# capacitive_touch_avr.net
KiCad netlist of a schematic drawn in EAGLE
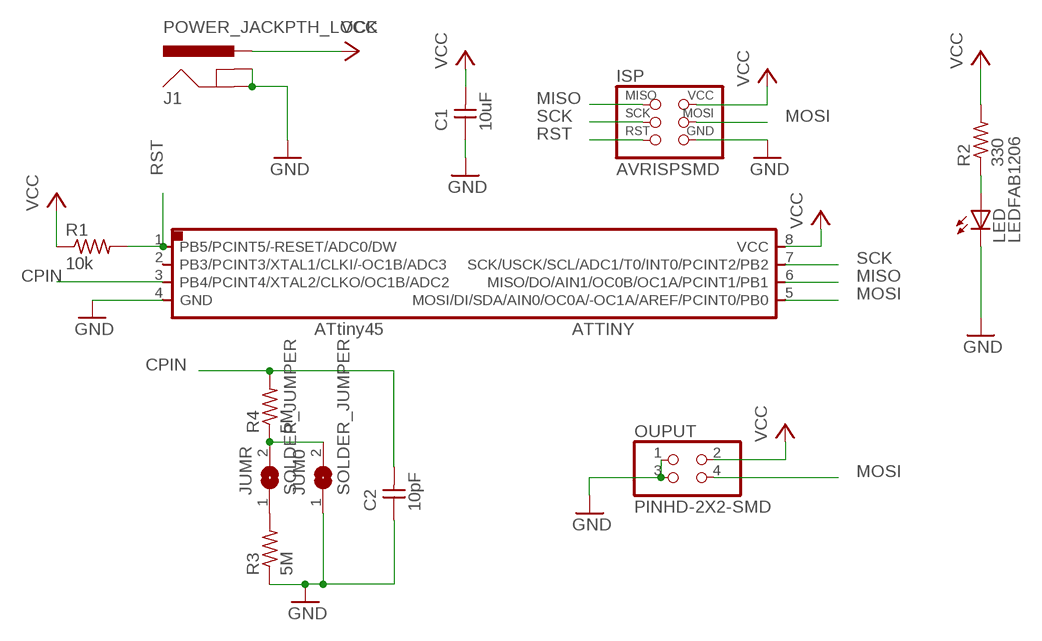
[diagram p0: schematic, sheet 1]

(export (version "E")
  (design (tool "Eeschema 10.0.6"))
  (components
    (comp (ref "ATTINY")
      (value "ATTINY45SI")
      (footprint "eagle-import:SOIC8")
      (libsource (lib "eagle-import") (part "ATTINY45SI"))
    )
    (comp (ref "C1")
      (value "10uF")
      (footprint "eagle-import:C1206FAB")
      (libsource (lib "eagle-import") (part "CAP-UNPOLARIZEDFAB"))
    )
    (comp (ref "C2")
      (value "10pF")
      (footprint "eagle-import:C1206FAB")
      (libsource (lib "eagle-import") (part "CAP-UNPOLARIZEDFAB"))
    )
    (comp (ref "ISP")
      (value "AVRISPSMD")
      (footprint "eagle-import:2X03SMD")
      (libsource (lib "eagle-import") (part "AVRISPSMD"))
    )
    (comp (ref "J1")
      (value "POWER_JACKPTH_LOCK")
      (footprint "eagle-import:POWER_JACK_PTH_LOCK")
      (libsource (lib "eagle-import") (part "POWER_JACKPTH_LOCK"))
    )
    (comp (ref "JUM0")
      (value "SOLDER_JUMPER")
      (footprint "eagle-import:SJFAB")
      (libsource (lib "eagle-import") (part "SOLDER_JUMPER"))
    )
    (comp (ref "JUMR")
      (value "SOLDER_JUMPER")
      (footprint "eagle-import:SJFAB")
      (libsource (lib "eagle-import") (part "SOLDER_JUMPER"))
    )
    (comp (ref "LED")
      (value "LEDFAB1206")
      (footprint "eagle-import:LED1206FAB")
      (libsource (lib "eagle-import") (part "LEDFAB1206"))
    )
    (comp (ref "OUPUT")
      (value "PINHD-2X2-SMD")
      (footprint "eagle-import:2X02SMD")
      (libsource (lib "eagle-import") (part "PINHD-2X2-SMD"))
    )
    (comp (ref "R1")
      (value "10k")
      (footprint "eagle-import:R1206FAB")
      (libsource (lib "eagle-import") (part "RES-US1206FAB"))
    )
    (comp (ref "R2")
      (value "330")
      (footprint "eagle-import:R1206FAB")
      (libsource (lib "eagle-import") (part "RES-US1206FAB"))
    )
    (comp (ref "R3")
      (value "5M")
      (footprint "eagle-import:R1206FAB")
      (libsource (lib "eagle-import") (part "RES-US1206FAB"))
    )
    (comp (ref "R4")
      (value "5M")
      (footprint "eagle-import:R1206FAB")
      (libsource (lib "eagle-import") (part "RES-US1206FAB"))
    )
  )
  (nets
    (net (code "1") (name "/CPIN") (class "Default")
      (node (ref "ATTINY") (pin "3") (pinfunction "PB4/PCINT4/XTAL2/CLKO/OC1B/ADC2_3") (pintype "bidirectional"))
      (node (ref "C2") (pin "2") (pinfunction "2_2") (pintype "passive"))
      (node (ref "R4") (pin "2") (pinfunction "2_2") (pintype "passive"))
    )
    (net (code "2") (name "/MISO") (class "Default")
      (node (ref "ATTINY") (pin "6") (pinfunction "MISO/DO/AIN1/OC0B/OC1A/PCINT1/PB1_6") (pintype "bidirectional"))
      (node (ref "ISP") (pin "1") (pinfunction "MISO_1") (pintype "passive"))
    )
    (net (code "3") (name "/MOSI") (class "Default")
      (node (ref "ATTINY") (pin "5") (pinfunction "MOSI/DI/SDA/AIN0/OC0A/-OC1A/AREF/PCINT0/PB0_5") (pintype "bidirectional"))
      (node (ref "ISP") (pin "4") (pinfunction "MOSI_4") (pintype "passive"))
      (node (ref "OUPUT") (pin "4") (pinfunction "4_4") (pintype "passive"))
    )
    (net (code "4") (name "/RST") (class "Default")
      (node (ref "ATTINY") (pin "1") (pinfunction "PB5/PCINT5/-RESET/ADC0/DW_1") (pintype "bidirectional"))
      (node (ref "ISP") (pin "5") (pinfunction "RST_5") (pintype "passive"))
      (node (ref "R1") (pin "2") (pinfunction "2_2") (pintype "passive"))
    )
    (net (code "5") (name "/SCK") (class "Default")
      (node (ref "ATTINY") (pin "7") (pinfunction "SCK/USCK/SCL/ADC1/T0/INT0/PCINT2/PB2_7") (pintype "bidirectional"))
      (node (ref "ISP") (pin "3") (pinfunction "SCK_3") (pintype "passive"))
    )
    (net (code "6") (name "GND") (class "Default")
      (node (ref "ATTINY") (pin "4") (pinfunction "GND_4") (pintype "bidirectional"))
      (node (ref "C1") (pin "1") (pinfunction "1_1") (pintype "passive"))
      (node (ref "C2") (pin "1") (pinfunction "1_1") (pintype "passive"))
      (node (ref "ISP") (pin "6") (pinfunction "GND_6") (pintype "passive"))
      (node (ref "J1") (pin "GND") (pinfunction "GND_GND") (pintype "bidirectional"))
      (node (ref "J1") (pin "GNDBREAK") (pinfunction "GNDBREAK_GNDBREAK") (pintype "bidirectional"))
      (node (ref "JUM0") (pin "1") (pinfunction "1_1") (pintype "passive"))
      (node (ref "LED") (pin "2") (pinfunction "C_2") (pintype "passive"))
      (node (ref "OUPUT") (pin "1") (pinfunction "1_1") (pintype "passive"))
      (node (ref "OUPUT") (pin "3") (pinfunction "3_3") (pintype "passive"))
      (node (ref "R3") (pin "1") (pinfunction "1_1") (pintype "passive"))
    )
    (net (code "7") (name "Net-(JUM0-Pad2)") (class "Default")
      (node (ref "JUM0") (pin "2") (pinfunction "2_2") (pintype "passive"))
      (node (ref "JUMR") (pin "2") (pinfunction "2_2") (pintype "passive"))
      (node (ref "R4") (pin "1") (pinfunction "1_1") (pintype "passive"))
    )
    (net (code "8") (name "Net-(JUMR-Pad1)") (class "Default")
      (node (ref "JUMR") (pin "1") (pinfunction "1_1") (pintype "passive"))
      (node (ref "R3") (pin "2") (pinfunction "2_2") (pintype "passive"))
    )
    (net (code "9") (name "Net-(LED-A)") (class "Default")
      (node (ref "LED") (pin "1") (pinfunction "A_1") (pintype "passive"))
      (node (ref "R2") (pin "1") (pinfunction "1_1") (pintype "passive"))
    )
    (net (code "10") (name "VCC") (class "Default")
      (node (ref "ATTINY") (pin "8") (pinfunction "VCC_8") (pintype "bidirectional"))
      (node (ref "C1") (pin "2") (pinfunction "2_2") (pintype "passive"))
      (node (ref "ISP") (pin "2") (pinfunction "VCC_2") (pintype "passive"))
      (node (ref "J1") (pin "PWR") (pinfunction "PWR_PWR") (pintype "bidirectional"))
      (node (ref "OUPUT") (pin "2") (pinfunction "2_2") (pintype "passive"))
      (node (ref "R1") (pin "1") (pinfunction "1_1") (pintype "passive"))
      (node (ref "R2") (pin "2") (pinfunction "2_2") (pintype "passive"))
    )
    (net (code "11") (name "unconnected-(ATTINY-PB3{slash}PCINT3{slash}XTAL1{slash}CLKI{slash}-OC1B{slash}ADC3-Pad2)") (class "Default")
      (node (ref "ATTINY") (pin "2") (pinfunction "PB3/PCINT3/XTAL1/CLKI/-OC1B/ADC3_2") (pintype "bidirectional"))
    )
  )
)
